# 04_-_SIM808.net
KiCad netlist of a schematic drawn in Altium Designer
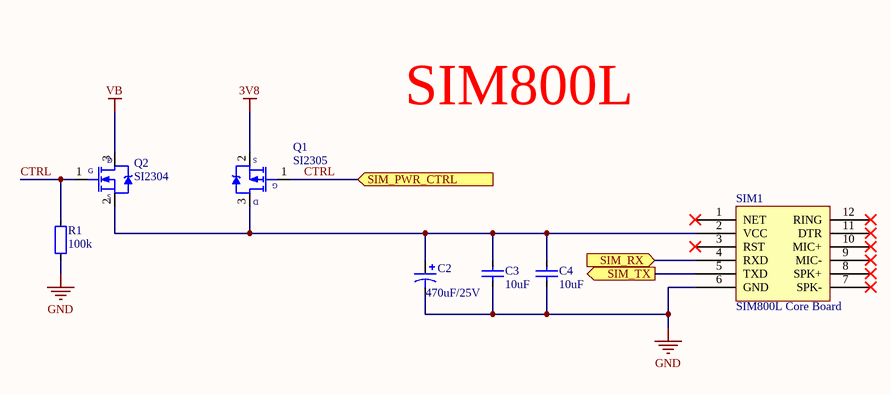
[diagram p0: [04] - SIM808.SchDoc]

(export (version "E")
  (design (tool "Eeschema 10.0.6"))
  (components
    (comp (ref "C2")
      (value "470uF/25V")
      (footprint "C8mm")
      (description "Polarized Capacitor (Axial)")
      (fields (field (name "PUBLISHER") "Altium Limited"))
      (libsource (lib "My Library") (part "Cap Pol"))
    )
    (comp (ref "C3")
      (value "10uF")
      (footprint "CAP_0805")
      (description "Capacitor")
      (fields (field (name "PUBLISHER") "Altium Limited"))
      (libsource (lib "My Library") (part "CapSMD"))
    )
    (comp (ref "C4")
      (value "10uF")
      (footprint "CAP_0805")
      (description "Capacitor")
      (fields (field (name "PUBLISHER") "Altium Limited"))
      (libsource (lib "My Library") (part "CapSMD"))
    )
    (comp (ref "Q1")
      (value "SI2305")
      (footprint "SOT23")
      (description "SI2305 A5SHB P-MOSFET 3.5A 8V SOT-23")
      (libsource (lib "My Library") (part "SI2305"))
    )
    (comp (ref "Q2")
      (value "SI2304")
      (footprint "SOT23")
      (description "SI2304 A4SHB N-MOSFET 3.6A 30V SOT-23")
      (libsource (lib "My Library") (part "SI2304"))
    )
    (comp (ref "R1")
      (value "100k")
      (footprint "RES-SMD-0805")
      (description "Resistor")
      (fields
        (field (name "MANUFACTURER") "Generic Components")
        (field (name "PUBLISHER") "Altium Hobart Technology Centre")
      )
      (libsource (lib "My Library") (part "Resistor - SMD"))
    )
    (comp (ref "SIM1")
      (value "SIM800L Core Board")
      (footprint "SIM800L Core Board")
      (libsource (lib "My Library") (part "SIM800L Core Board"))
    )
  )
  (nets
    (net (code "1") (name "/CTRL") (class "Default")
      (node (ref "Q1") (pin "1") (pinfunction "G_1") (pintype "passive"))
      (node (ref "Q2") (pin "1") (pinfunction "G_1") (pintype "passive"))
      (node (ref "R1") (pin "2") (pinfunction "2_2") (pintype "passive"))
    )
    (net (code "2") (name "/SIM_RX") (class "Default")
      (node (ref "SIM1") (pin "4") (pinfunction "RXD_4") (pintype "passive"))
    )
    (net (code "3") (name "/SIM_TX") (class "Default")
      (node (ref "SIM1") (pin "5") (pinfunction "TXD_5") (pintype "passive"))
    )
    (net (code "4") (name "3V8") (class "Default")
      (node (ref "Q1") (pin "2") (pinfunction "S_2") (pintype "passive"))
    )
    (net (code "5") (name "GND") (class "Default")
      (node (ref "C2") (pin "2") (pinfunction "2_2") (pintype "passive"))
      (node (ref "C3") (pin "1") (pinfunction "1_1") (pintype "passive"))
      (node (ref "C4") (pin "1") (pinfunction "1_1") (pintype "passive"))
      (node (ref "R1") (pin "1") (pinfunction "1_1") (pintype "passive"))
      (node (ref "SIM1") (pin "6") (pinfunction "GND_6") (pintype "passive"))
    )
    (net (code "6") (name "Net-(Q1-D)") (class "Default")
      (node (ref "C2") (pin "1") (pinfunction "1_1") (pintype "passive"))
      (node (ref "C3") (pin "2") (pinfunction "2_2") (pintype "passive"))
      (node (ref "C4") (pin "2") (pinfunction "2_2") (pintype "passive"))
      (node (ref "Q1") (pin "3") (pinfunction "D_3") (pintype "passive"))
      (node (ref "Q2") (pin "2") (pinfunction "S_2") (pintype "passive"))
      (node (ref "SIM1") (pin "2") (pinfunction "VCC_2") (pintype "passive"))
    )
    (net (code "7") (name "VB") (class "Default")
      (node (ref "Q2") (pin "3") (pinfunction "D_3") (pintype "passive"))
    )
    (net (code "8") (name "unconnected-(SIM1-DTR-Pad11)") (class "Default")
      (node (ref "SIM1") (pin "11") (pinfunction "DTR_11") (pintype "passive+no_connect"))
    )
    (net (code "9") (name "unconnected-(SIM1-MIC+-Pad10)") (class "Default")
      (node (ref "SIM1") (pin "10") (pinfunction "MIC+_10") (pintype "passive+no_connect"))
    )
    (net (code "10") (name "unconnected-(SIM1-MIC--Pad9)") (class "Default")
      (node (ref "SIM1") (pin "9") (pinfunction "MIC-_9") (pintype "passive+no_connect"))
    )
    (net (code "11") (name "unconnected-(SIM1-NET-Pad1)") (class "Default")
      (node (ref "SIM1") (pin "1") (pinfunction "NET_1") (pintype "passive+no_connect"))
    )
    (net (code "12") (name "unconnected-(SIM1-RING-Pad12)") (class "Default")
      (node (ref "SIM1") (pin "12") (pinfunction "RING_12") (pintype "passive+no_connect"))
    )
    (net (code "13") (name "unconnected-(SIM1-RST-Pad3)") (class "Default")
      (node (ref "SIM1") (pin "3") (pinfunction "RST_3") (pintype "passive+no_connect"))
    )
    (net (code "14") (name "unconnected-(SIM1-SPK+-Pad8)") (class "Default")
      (node (ref "SIM1") (pin "8") (pinfunction "SPK+_8") (pintype "passive+no_connect"))
    )
    (net (code "15") (name "unconnected-(SIM1-SPK--Pad7)") (class "Default")
      (node (ref "SIM1") (pin "7") (pinfunction "SPK-_7") (pintype "passive+no_connect"))
    )
  )
)
